# 3-6.net
KiCad netlist of a schematic drawn in Altium Designer
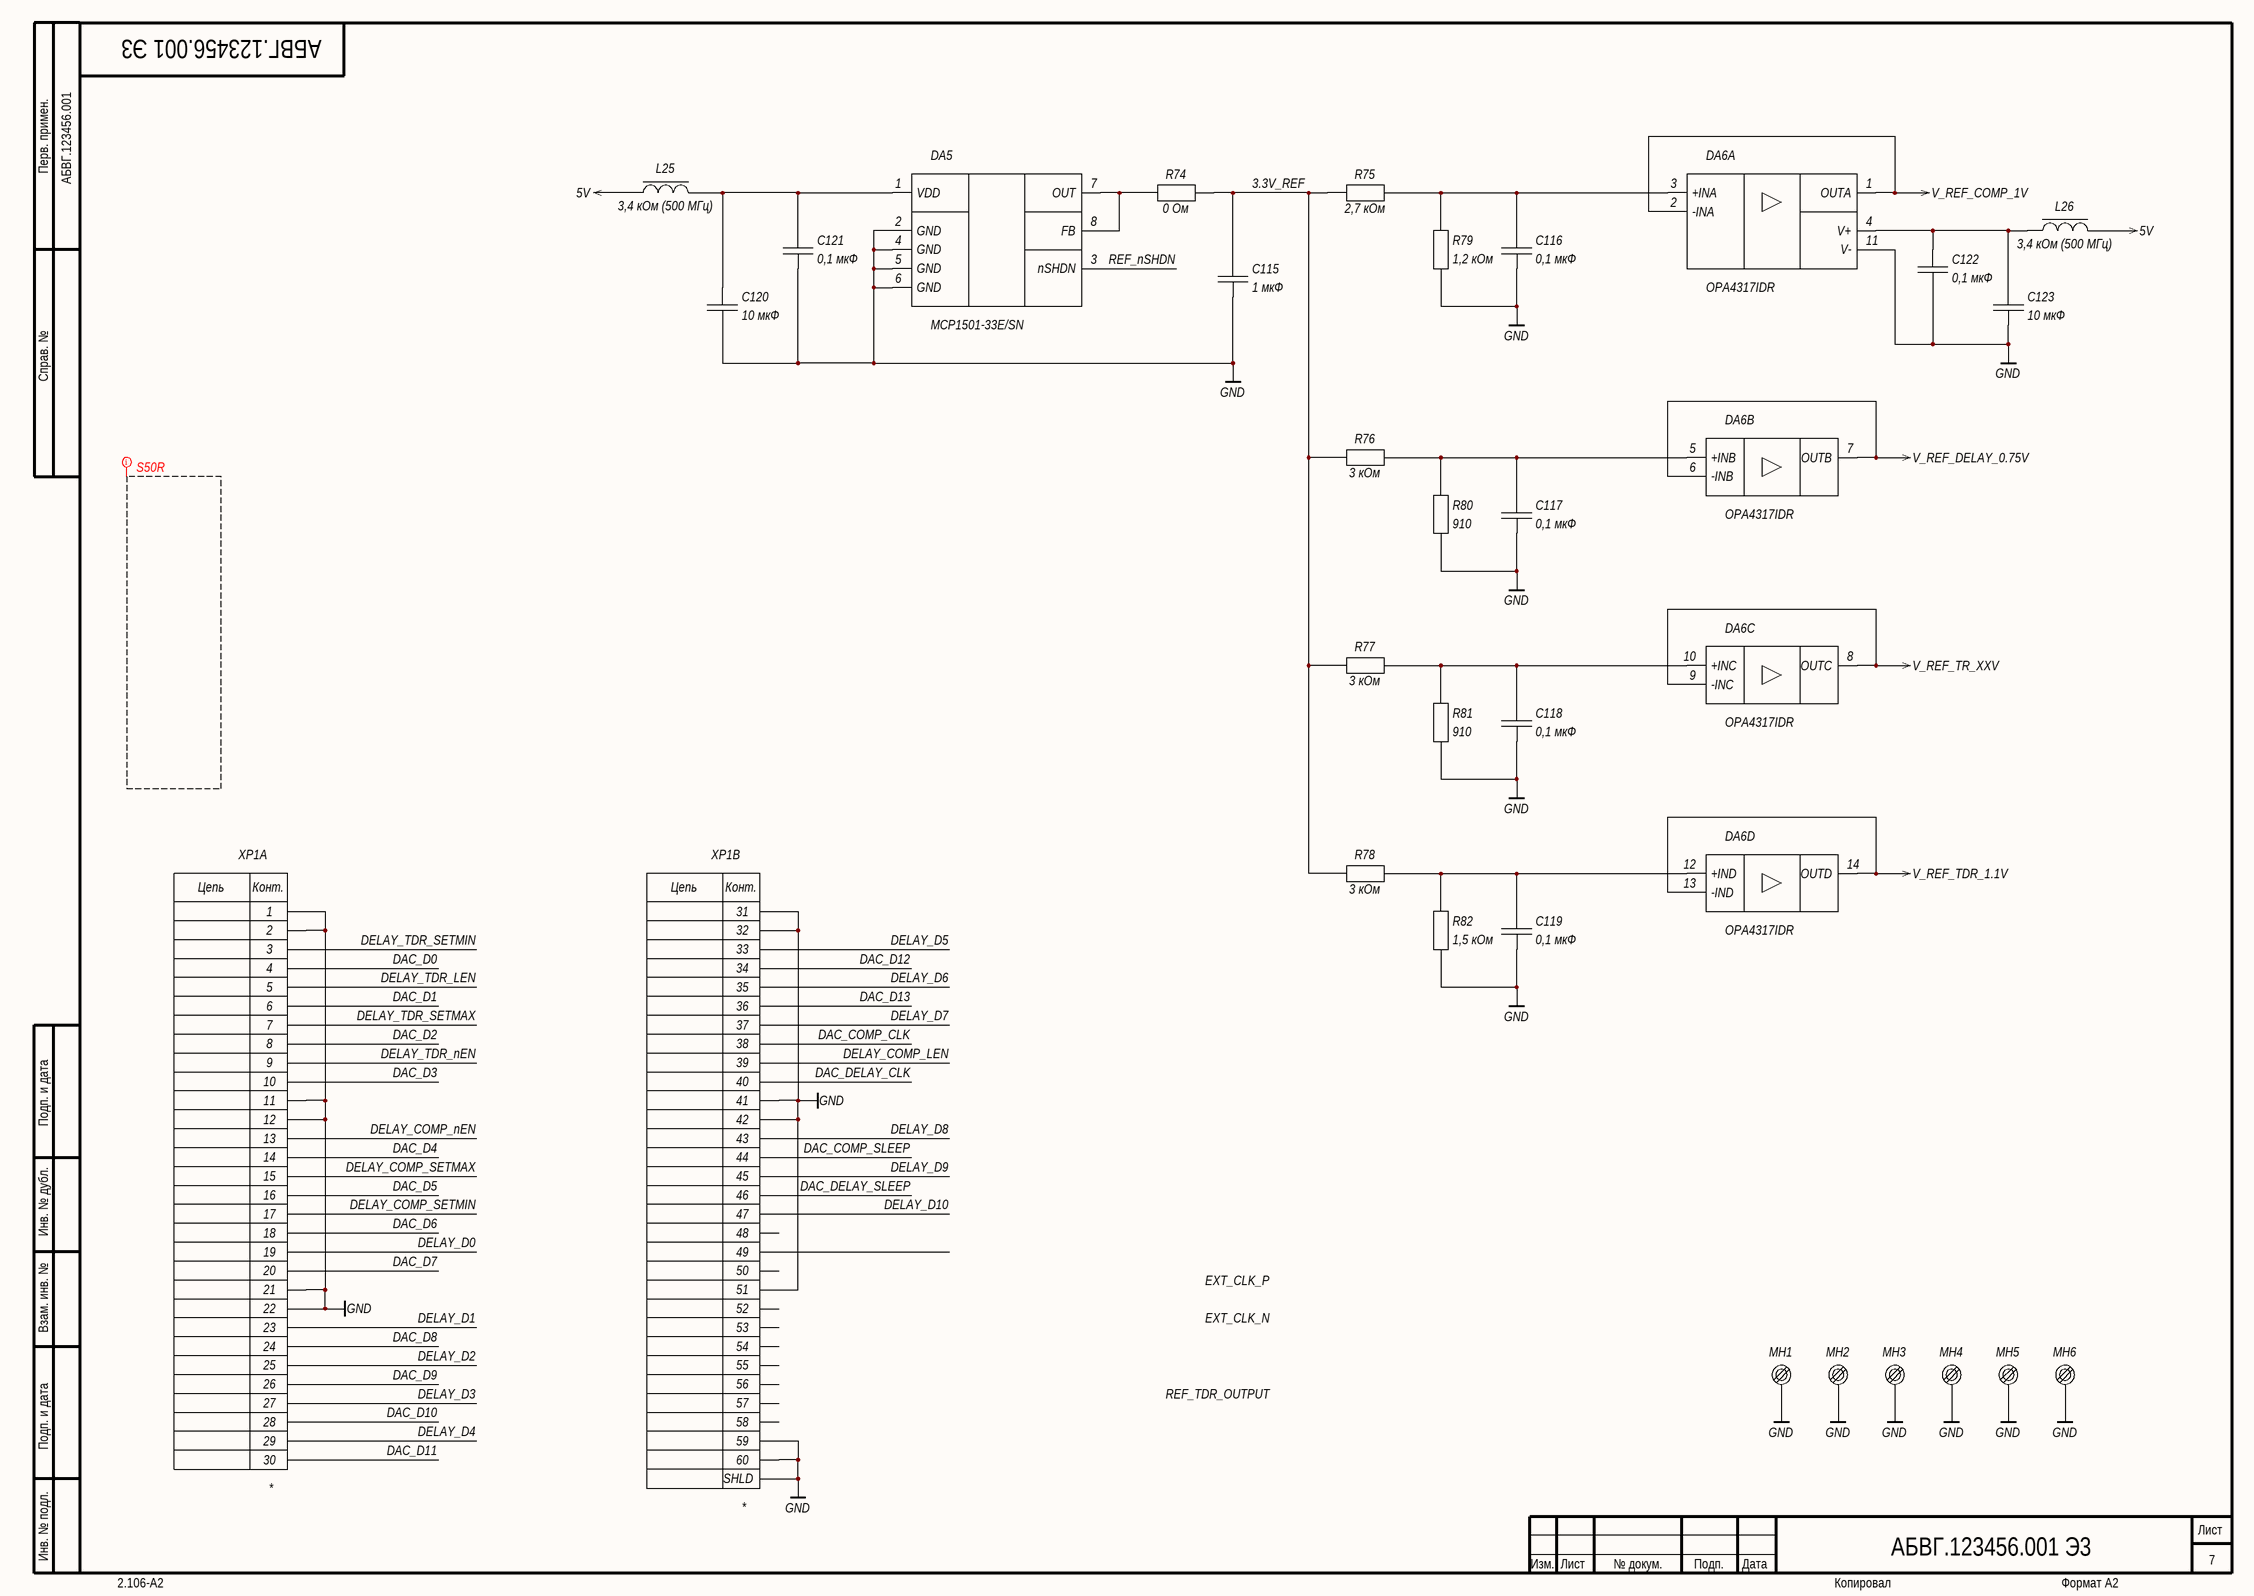
[diagram p0: Э3-6 Электропитание.SchDoc]

(export (version "E")
  (design (tool "Eeschema 10.0.6"))
  (components
    (comp (ref "C115")
      (value "1 мкФ")
      (footprint "C0402-B-0.5mm")
      (description "0402 X7R 1 мкФ ±10 % 25 В")
      (libsource (lib "Capacitors") (part "Non Polar Ver."))
    )
    (comp (ref "C116")
      (value "0,1 мкФ")
      (footprint "C0402-B-0.5mm")
      (description "0402 X7R 0,1 мкФ ±10 % 50 В")
      (libsource (lib "Capacitors") (part "Non Polar Ver."))
    )
    (comp (ref "C117")
      (value "0,1 мкФ")
      (footprint "C0402-B-0.5mm")
      (description "0402 X7R 0,1 мкФ ±10 % 50 В")
      (libsource (lib "Capacitors") (part "Non Polar Ver."))
    )
    (comp (ref "C118")
      (value "0,1 мкФ")
      (footprint "C0402-B-0.5mm")
      (description "0402 X7R 0,1 мкФ ±10 % 50 В")
      (libsource (lib "Capacitors") (part "Non Polar Ver."))
    )
    (comp (ref "C119")
      (value "0,1 мкФ")
      (footprint "C0402-B-0.5mm")
      (description "0402 X7R 0,1 мкФ ±10 % 50 В")
      (libsource (lib "Capacitors") (part "Non Polar Ver."))
    )
    (comp (ref "C120")
      (value "10 мкФ")
      (footprint "C0603-B-0.8mm")
      (description "0603 X5R 10 мкФ ±20 % 25 В")
      (fields (field (name "PARTNUMBER") "GRM188R61E106MA73"))
      (libsource (lib "Capacitors") (part "Non Polar Ver."))
    )
    (comp (ref "C121")
      (value "0,1 мкФ")
      (footprint "C0402-B-0.5mm")
      (description "0402 X7R 0,1 мкФ ±10 % 50 В")
      (fields (field (name "PARTNUMBER") "GRM155R71H104KE14D"))
      (libsource (lib "Capacitors") (part "Non Polar Ver."))
    )
    (comp (ref "C122")
      (value "0,1 мкФ")
      (footprint "C0402-B-0.5mm")
      (description "0402 X7R 0,1 мкФ ±10 % 50 В")
      (fields (field (name "PARTNUMBER") "GRM155R71H104KE14D"))
      (libsource (lib "Capacitors") (part "Non Polar Ver."))
    )
    (comp (ref "C123")
      (value "10 мкФ")
      (footprint "C0603-B-0.8mm")
      (description "0603 X5R 10 мкФ ±20 % 25 В")
      (fields (field (name "PARTNUMBER") "GRM188R61E106MA73"))
      (libsource (lib "Capacitors") (part "Non Polar Ver."))
    )
    (comp (ref "DA5")
      (value "MCP1501-33E/SN")
      (footprint "8-SOIC-3.9")
      (description "High Precision Buffered Voltage Reference")
      (libsource (lib "Power") (part "MCP1501-XXE/SN"))
    )
    (comp (ref "DA6")
      (value "OPA4317IDR")
      (footprint "14-SOIC-3.9")
      (description "Zerø-Drift, Low-Offset, Rail-to-Rail I/O Operational Amplifier")
      (fields (field (name "MANUFACTURER") "Texas Instruments"))
      (libsource (lib "Analog") (part "OPA4317"))
    )
    (comp (ref "L25")
      (value "3,4 кОм (500 МГц)")
      (footprint "L0402-B-0.5mm")
      (fields (field (name "PARTNUMBER") "BLM15HD182BH1"))
      (libsource (lib "Inductors") (part "Inductor MC Hor."))
    )
    (comp (ref "L26")
      (value "3,4 кОм (500 МГц)")
      (footprint "L0402-B-0.5mm")
      (fields (field (name "PARTNUMBER") "BLM15HD182BH1"))
      (libsource (lib "Inductors") (part "Inductor MC Hor."))
    )
    (comp (ref "MH1")
      (value "Mechanical Connection")
      (footprint "Отверстие 2,4x5")
      (libsource (lib "Mechanics") (part "Mechanical Connection"))
    )
    (comp (ref "MH2")
      (value "Mechanical Connection")
      (footprint "Отверстие 2,4x5")
      (libsource (lib "Mechanics") (part "Mechanical Connection"))
    )
    (comp (ref "MH3")
      (value "Mechanical Connection")
      (footprint "Отверстие 2,4x5")
      (libsource (lib "Mechanics") (part "Mechanical Connection"))
    )
    (comp (ref "MH4")
      (value "Mechanical Connection")
      (footprint "Отверстие 2,4x5")
      (libsource (lib "Mechanics") (part "Mechanical Connection"))
    )
    (comp (ref "MH5")
      (value "Mechanical Connection")
      (footprint "Отверстие 2,4x5")
      (libsource (lib "Mechanics") (part "Mechanical Connection"))
    )
    (comp (ref "MH6")
      (value "Mechanical Connection")
      (footprint "Отверстие 2,4x5")
      (libsource (lib "Mechanics") (part "Mechanical Connection"))
    )
    (comp (ref "R74")
      (value "0 Ом")
      (footprint "CR0402-B-0.35mm")
      (libsource (lib "Resistors") (part "Resistor Hor."))
    )
    (comp (ref "R75")
      (value "2,7 кОм")
      (footprint "CR0402-B-0.35mm")
      (description "0402 2,7 кОм ±1 %")
      (libsource (lib "Resistors") (part "Resistor Hor."))
    )
    (comp (ref "R76")
      (value "3 кОм")
      (footprint "CR0402-B-0.35mm")
      (description "0402 3 кОм ±1 %")
      (libsource (lib "Resistors") (part "Resistor Hor."))
    )
    (comp (ref "R77")
      (value "3 кОм")
      (footprint "CR0402-B-0.35mm")
      (description "0402 3 кОм ±1 %")
      (libsource (lib "Resistors") (part "Resistor Hor."))
    )
    (comp (ref "R78")
      (value "3 кОм")
      (footprint "CR0402-B-0.35mm")
      (description "0402 3 кОм ±1 %")
      (libsource (lib "Resistors") (part "Resistor Hor."))
    )
    (comp (ref "R79")
      (value "1,2 кОм")
      (footprint "CR0402-B-0.35mm")
      (description "0402 1,2 кОм ±1 %")
      (libsource (lib "Resistors") (part "Resistor Ver."))
    )
    (comp (ref "R80")
      (value "910")
      (footprint "CR0402-B-0.35mm")
      (description "0402 910 Ом ±1 %")
      (libsource (lib "Resistors") (part "Resistor Ver."))
    )
    (comp (ref "R81")
      (value "910")
      (footprint "CR0402-B-0.35mm")
      (description "0402 910 Ом ±1 %")
      (libsource (lib "Resistors") (part "Resistor Ver."))
    )
    (comp (ref "R82")
      (value "1,5 кОм")
      (footprint "CR0402-B-0.35mm")
      (description "0402 1,5 кОм ±1 %")
      (libsource (lib "Resistors") (part "Resistor Ver."))
    )
    (comp (ref "XP1")
      (value "*")
      (footprint "AXT460324")
      (libsource (lib "Connectors") (part "XP_60_SHLD_Pin_Open"))
    )
  )
  (nets
    (net (code "1") (name "/3.3V_REF") (class "Default")
      (node (ref "C115") (pin "1") (pinfunction "1_1") (pintype "passive"))
      (node (ref "R74") (pin "2") (pinfunction "2_2") (pintype "passive"))
      (node (ref "R75") (pin "1") (pinfunction "1_1") (pintype "passive"))
      (node (ref "R76") (pin "1") (pinfunction "1_1") (pintype "passive"))
      (node (ref "R77") (pin "1") (pinfunction "1_1") (pintype "passive"))
      (node (ref "R78") (pin "1") (pinfunction "1_1") (pintype "passive"))
    )
    (net (code "2") (name "/DAC_COMP_CLK") (class "Default")
      (node (ref "XP1") (pin "38") (pinfunction "38_38") (pintype "passive"))
    )
    (net (code "3") (name "/DAC_COMP_SLEEP") (class "Default")
      (node (ref "XP1") (pin "44") (pinfunction "44_44") (pintype "passive"))
    )
    (net (code "4") (name "/DAC_D0") (class "Default")
      (node (ref "XP1") (pin "4") (pinfunction "4_4") (pintype "passive"))
    )
    (net (code "5") (name "/DAC_D1") (class "Default")
      (node (ref "XP1") (pin "6") (pinfunction "6_6") (pintype "passive"))
    )
    (net (code "6") (name "/DAC_D2") (class "Default")
      (node (ref "XP1") (pin "8") (pinfunction "8_8") (pintype "passive"))
    )
    (net (code "7") (name "/DAC_D3") (class "Default")
      (node (ref "XP1") (pin "10") (pinfunction "10_10") (pintype "passive"))
    )
    (net (code "8") (name "/DAC_D4") (class "Default")
      (node (ref "XP1") (pin "14") (pinfunction "14_14") (pintype "passive"))
    )
    (net (code "9") (name "/DAC_D5") (class "Default")
      (node (ref "XP1") (pin "16") (pinfunction "16_16") (pintype "passive"))
    )
    (net (code "10") (name "/DAC_D6") (class "Default")
      (node (ref "XP1") (pin "18") (pinfunction "18_18") (pintype "passive"))
    )
    (net (code "11") (name "/DAC_D7") (class "Default")
      (node (ref "XP1") (pin "20") (pinfunction "20_20") (pintype "passive"))
    )
    (net (code "12") (name "/DAC_D8") (class "Default")
      (node (ref "XP1") (pin "24") (pinfunction "24_24") (pintype "passive"))
    )
    (net (code "13") (name "/DAC_D9") (class "Default")
      (node (ref "XP1") (pin "26") (pinfunction "26_26") (pintype "passive"))
    )
    (net (code "14") (name "/DAC_D10") (class "Default")
      (node (ref "XP1") (pin "28") (pinfunction "28_28") (pintype "passive"))
    )
    (net (code "15") (name "/DAC_D11") (class "Default")
      (node (ref "XP1") (pin "30") (pinfunction "30_30") (pintype "passive"))
    )
    (net (code "16") (name "/DAC_D12") (class "Default")
      (node (ref "XP1") (pin "34") (pinfunction "34_34") (pintype "passive"))
    )
    (net (code "17") (name "/DAC_D13") (class "Default")
      (node (ref "XP1") (pin "36") (pinfunction "36_36") (pintype "passive"))
    )
    (net (code "18") (name "/DAC_DELAY_CLK") (class "Default")
      (node (ref "XP1") (pin "40") (pinfunction "40_40") (pintype "passive"))
    )
    (net (code "19") (name "/DAC_DELAY_SLEEP") (class "Default")
      (node (ref "XP1") (pin "46") (pinfunction "46_46") (pintype "passive"))
    )
    (net (code "20") (name "/DELAY_COMP_LEN") (class "Default")
      (node (ref "XP1") (pin "39") (pinfunction "39_39") (pintype "passive"))
    )
    (net (code "21") (name "/DELAY_COMP_SETMAX") (class "Default")
      (node (ref "XP1") (pin "15") (pinfunction "15_15") (pintype "passive"))
    )
    (net (code "22") (name "/DELAY_COMP_SETMIN") (class "Default")
      (node (ref "XP1") (pin "17") (pinfunction "17_17") (pintype "passive"))
    )
    (net (code "23") (name "/DELAY_COMP_nEN") (class "Default")
      (node (ref "XP1") (pin "13") (pinfunction "13_13") (pintype "passive"))
    )
    (net (code "24") (name "/DELAY_D0") (class "Default")
      (node (ref "XP1") (pin "19") (pinfunction "19_19") (pintype "passive"))
    )
    (net (code "25") (name "/DELAY_D1") (class "Default")
      (node (ref "XP1") (pin "23") (pinfunction "23_23") (pintype "passive"))
    )
    (net (code "26") (name "/DELAY_D2") (class "Default")
      (node (ref "XP1") (pin "25") (pinfunction "25_25") (pintype "passive"))
    )
    (net (code "27") (name "/DELAY_D3") (class "Default")
      (node (ref "XP1") (pin "27") (pinfunction "27_27") (pintype "passive"))
    )
    (net (code "28") (name "/DELAY_D4") (class "Default")
      (node (ref "XP1") (pin "29") (pinfunction "29_29") (pintype "passive"))
    )
    (net (code "29") (name "/DELAY_D5") (class "Default")
      (node (ref "XP1") (pin "33") (pinfunction "33_33") (pintype "passive"))
    )
    (net (code "30") (name "/DELAY_D6") (class "Default")
      (node (ref "XP1") (pin "35") (pinfunction "35_35") (pintype "passive"))
    )
    (net (code "31") (name "/DELAY_D7") (class "Default")
      (node (ref "XP1") (pin "37") (pinfunction "37_37") (pintype "passive"))
    )
    (net (code "32") (name "/DELAY_D8") (class "Default")
      (node (ref "XP1") (pin "43") (pinfunction "43_43") (pintype "passive"))
    )
    (net (code "33") (name "/DELAY_D9") (class "Default")
      (node (ref "XP1") (pin "45") (pinfunction "45_45") (pintype "passive"))
    )
    (net (code "34") (name "/DELAY_D10") (class "Default")
      (node (ref "XP1") (pin "47") (pinfunction "47_47") (pintype "passive"))
    )
    (net (code "35") (name "/DELAY_TDR_LEN") (class "Default")
      (node (ref "XP1") (pin "5") (pinfunction "5_5") (pintype "passive"))
    )
    (net (code "36") (name "/DELAY_TDR_SETMAX") (class "Default")
      (node (ref "XP1") (pin "7") (pinfunction "7_7") (pintype "passive"))
    )
    (net (code "37") (name "/DELAY_TDR_SETMIN") (class "Default")
      (node (ref "XP1") (pin "3") (pinfunction "3_3") (pintype "passive"))
    )
    (net (code "38") (name "/DELAY_TDR_nEN") (class "Default")
      (node (ref "XP1") (pin "9") (pinfunction "9_9") (pintype "passive"))
    )
    (net (code "42") (name "/REF_nSHDN") (class "Default")
      (node (ref "DA5") (pin "3") (pinfunction "nSHDN_3") (pintype "passive"))
    )
    (net (code "43") (name "5V") (class "Default")
      (node (ref "L25") (pin "1") (pinfunction "1_1") (pintype "passive"))
      (node (ref "L26") (pin "2") (pinfunction "2_2") (pintype "passive"))
    )
    (net (code "44") (name "GND") (class "Default")
      (node (ref "C115") (pin "2") (pinfunction "2_2") (pintype "passive"))
      (node (ref "C116") (pin "2") (pinfunction "2_2") (pintype "passive"))
      (node (ref "C117") (pin "2") (pinfunction "2_2") (pintype "passive"))
      (node (ref "C118") (pin "2") (pinfunction "2_2") (pintype "passive"))
      (node (ref "C119") (pin "2") (pinfunction "2_2") (pintype "passive"))
      (node (ref "C120") (pin "2") (pinfunction "2_2") (pintype "passive"))
      (node (ref "C121") (pin "2") (pinfunction "2_2") (pintype "passive"))
      (node (ref "C122") (pin "2") (pinfunction "2_2") (pintype "passive"))
      (node (ref "C123") (pin "2") (pinfunction "2_2") (pintype "passive"))
      (node (ref "DA5") (pin "2") (pinfunction "GND_2") (pintype "passive"))
      (node (ref "DA5") (pin "4") (pinfunction "GND_4") (pintype "passive"))
      (node (ref "DA5") (pin "5") (pinfunction "GND_5") (pintype "passive"))
      (node (ref "DA5") (pin "6") (pinfunction "GND_6") (pintype "passive"))
      (node (ref "DA6") (pin "11") (pinfunction "V-_11") (pintype "passive"))
      (node (ref "MH1") (pin "0") (pinfunction "0_0") (pintype "passive"))
      (node (ref "MH2") (pin "0") (pinfunction "0_0") (pintype "passive"))
      (node (ref "MH3") (pin "0") (pinfunction "0_0") (pintype "passive"))
      (node (ref "MH4") (pin "0") (pinfunction "0_0") (pintype "passive"))
      (node (ref "MH5") (pin "0") (pinfunction "0_0") (pintype "passive"))
      (node (ref "MH6") (pin "0") (pinfunction "0_0") (pintype "passive"))
      (node (ref "R79") (pin "2") (pinfunction "2_2") (pintype "passive"))
      (node (ref "R80") (pin "2") (pinfunction "2_2") (pintype "passive"))
      (node (ref "R81") (pin "2") (pinfunction "2_2") (pintype "passive"))
      (node (ref "R82") (pin "2") (pinfunction "2_2") (pintype "passive"))
      (node (ref "XP1") (pin "1") (pinfunction "1_1") (pintype "passive"))
      (node (ref "XP1") (pin "11") (pinfunction "11_11") (pintype "passive"))
      (node (ref "XP1") (pin "12") (pinfunction "12_12") (pintype "passive"))
      (node (ref "XP1") (pin "2") (pinfunction "2_2") (pintype "passive"))
      (node (ref "XP1") (pin "21") (pinfunction "21_21") (pintype "passive"))
      (node (ref "XP1") (pin "22") (pinfunction "22_22") (pintype "passive"))
      (node (ref "XP1") (pin "31") (pinfunction "31_31") (pintype "passive"))
      (node (ref "XP1") (pin "32") (pinfunction "32_32") (pintype "passive"))
      (node (ref "XP1") (pin "41") (pinfunction "41_41") (pintype "passive"))
      (node (ref "XP1") (pin "42") (pinfunction "42_42") (pintype "passive"))
      (node (ref "XP1") (pin "51") (pinfunction "51_51") (pintype "passive"))
      (node (ref "XP1") (pin "59") (pinfunction "59_59") (pintype "passive"))
      (node (ref "XP1") (pin "60") (pinfunction "60_60") (pintype "passive"))
      (node (ref "XP1") (pin "SHLD") (pinfunction "SHLD_SHLD") (pintype "passive"))
    )
    (net (code "45") (name "Net-(DA5-FB)") (class "Default")
      (node (ref "DA5") (pin "7") (pinfunction "OUT_7") (pintype "passive"))
      (node (ref "DA5") (pin "8") (pinfunction "FB_8") (pintype "passive"))
      (node (ref "R74") (pin "1") (pinfunction "1_1") (pintype "passive"))
    )
    (net (code "46") (name "Net-(DA5-VDD)") (class "Default")
      (node (ref "C120") (pin "1") (pinfunction "1_1") (pintype "passive"))
      (node (ref "C121") (pin "1") (pinfunction "1_1") (pintype "passive"))
      (node (ref "DA5") (pin "1") (pinfunction "VDD_1") (pintype "passive"))
      (node (ref "L25") (pin "2") (pinfunction "2_2") (pintype "passive"))
    )
    (net (code "47") (name "Net-(DA6A-+INA)") (class "Default")
      (node (ref "C116") (pin "1") (pinfunction "1_1") (pintype "passive"))
      (node (ref "DA6") (pin "3") (pinfunction "+INA_3") (pintype "passive"))
      (node (ref "R75") (pin "2") (pinfunction "2_2") (pintype "passive"))
      (node (ref "R79") (pin "1") (pinfunction "1_1") (pintype "passive"))
    )
    (net (code "48") (name "Net-(DA6A-V+)") (class "Default")
      (node (ref "C122") (pin "1") (pinfunction "1_1") (pintype "passive"))
      (node (ref "C123") (pin "1") (pinfunction "1_1") (pintype "passive"))
      (node (ref "DA6") (pin "4") (pinfunction "V+_4") (pintype "passive"))
      (node (ref "L26") (pin "1") (pinfunction "1_1") (pintype "passive"))
    )
    (net (code "49") (name "Net-(DA6B-+INB)") (class "Default")
      (node (ref "C117") (pin "1") (pinfunction "1_1") (pintype "passive"))
      (node (ref "DA6") (pin "5") (pinfunction "+INB_5") (pintype "passive"))
      (node (ref "R76") (pin "2") (pinfunction "2_2") (pintype "passive"))
      (node (ref "R80") (pin "1") (pinfunction "1_1") (pintype "passive"))
    )
    (net (code "50") (name "Net-(DA6C-+INC)") (class "Default")
      (node (ref "C118") (pin "1") (pinfunction "1_1") (pintype "passive"))
      (node (ref "DA6") (pin "10") (pinfunction "+INC_10") (pintype "passive"))
      (node (ref "R77") (pin "2") (pinfunction "2_2") (pintype "passive"))
      (node (ref "R81") (pin "1") (pinfunction "1_1") (pintype "passive"))
    )
    (net (code "51") (name "Net-(DA6D-+IND)") (class "Default")
      (node (ref "C119") (pin "1") (pinfunction "1_1") (pintype "passive"))
      (node (ref "DA6") (pin "12") (pinfunction "+IND_12") (pintype "passive"))
      (node (ref "R78") (pin "2") (pinfunction "2_2") (pintype "passive"))
      (node (ref "R82") (pin "1") (pinfunction "1_1") (pintype "passive"))
    )
    (net (code "52") (name "V_REF_COMP_1V") (class "Default")
      (node (ref "DA6") (pin "1") (pinfunction "OUTA_1") (pintype "passive"))
      (node (ref "DA6") (pin "2") (pinfunction "-INA_2") (pintype "passive"))
    )
    (net (code "53") (name "V_REF_DELAY_0.75V") (class "Default")
      (node (ref "DA6") (pin "6") (pinfunction "-INB_6") (pintype "passive"))
      (node (ref "DA6") (pin "7") (pinfunction "OUTB_7") (pintype "passive"))
    )
    (net (code "54") (name "V_REF_TDR_1.1V") (class "Default")
      (node (ref "DA6") (pin "13") (pinfunction "-IND_13") (pintype "passive"))
      (node (ref "DA6") (pin "14") (pinfunction "OUTD_14") (pintype "passive"))
    )
    (net (code "55") (name "V_REF_TR_XXV") (class "Default")
      (node (ref "DA6") (pin "8") (pinfunction "OUTC_8") (pintype "passive"))
      (node (ref "DA6") (pin "9") (pinfunction "-INC_9") (pintype "passive"))
    )
    (net (code "56") (name "unconnected-(XP1-Pad48)") (class "Default")
      (node (ref "XP1") (pin "48") (pinfunction "48_48") (pintype "passive"))
    )
    (net (code "57") (name "unconnected-(XP1-Pad49)") (class "Default")
      (node (ref "XP1") (pin "49") (pinfunction "49_49") (pintype "passive"))
    )
    (net (code "58") (name "unconnected-(XP1-Pad50)") (class "Default")
      (node (ref "XP1") (pin "50") (pinfunction "50_50") (pintype "passive"))
    )
    (net (code "59") (name "unconnected-(XP1-Pad52)") (class "Default")
      (node (ref "XP1") (pin "52") (pinfunction "52_52") (pintype "passive"))
    )
    (net (code "60") (name "unconnected-(XP1-Pad53)") (class "Default")
      (node (ref "XP1") (pin "53") (pinfunction "53_53") (pintype "passive"))
    )
    (net (code "61") (name "unconnected-(XP1-Pad54)") (class "Default")
      (node (ref "XP1") (pin "54") (pinfunction "54_54") (pintype "passive"))
    )
    (net (code "62") (name "unconnected-(XP1-Pad55)") (class "Default")
      (node (ref "XP1") (pin "55") (pinfunction "55_55") (pintype "passive"))
    )
    (net (code "63") (name "unconnected-(XP1-Pad56)") (class "Default")
      (node (ref "XP1") (pin "56") (pinfunction "56_56") (pintype "passive"))
    )
    (net (code "64") (name "unconnected-(XP1-Pad57)") (class "Default")
      (node (ref "XP1") (pin "57") (pinfunction "57_57") (pintype "passive"))
    )
    (net (code "65") (name "unconnected-(XP1-Pad58)") (class "Default")
      (node (ref "XP1") (pin "58") (pinfunction "58_58") (pintype "passive"))
    )
  )
)
